# EEZ_DIB_PREL6_r1B4.net
KiCad netlist of a schematic drawn in EAGLE
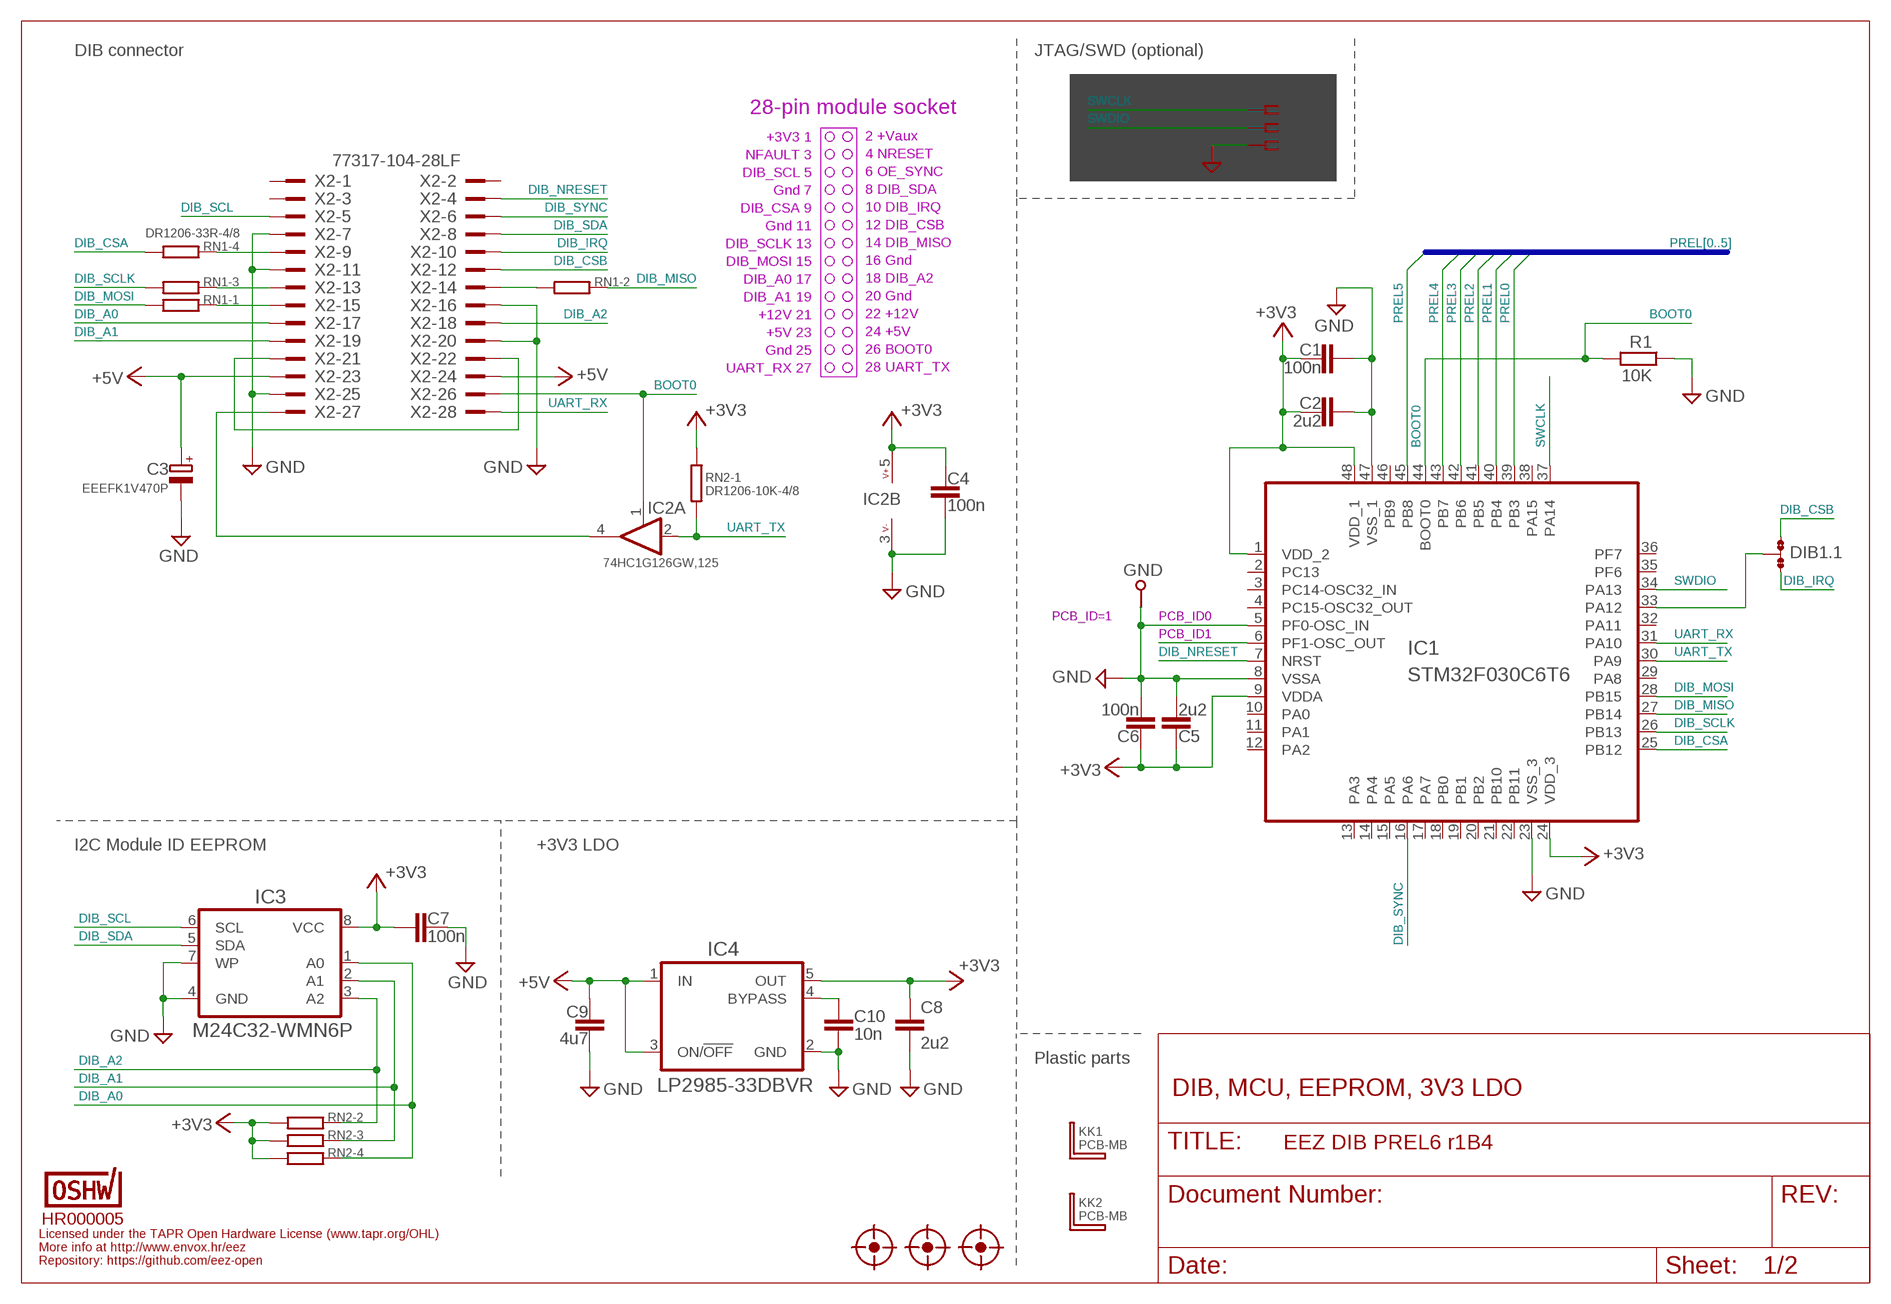
[diagram p0: schematic, sheet 1]
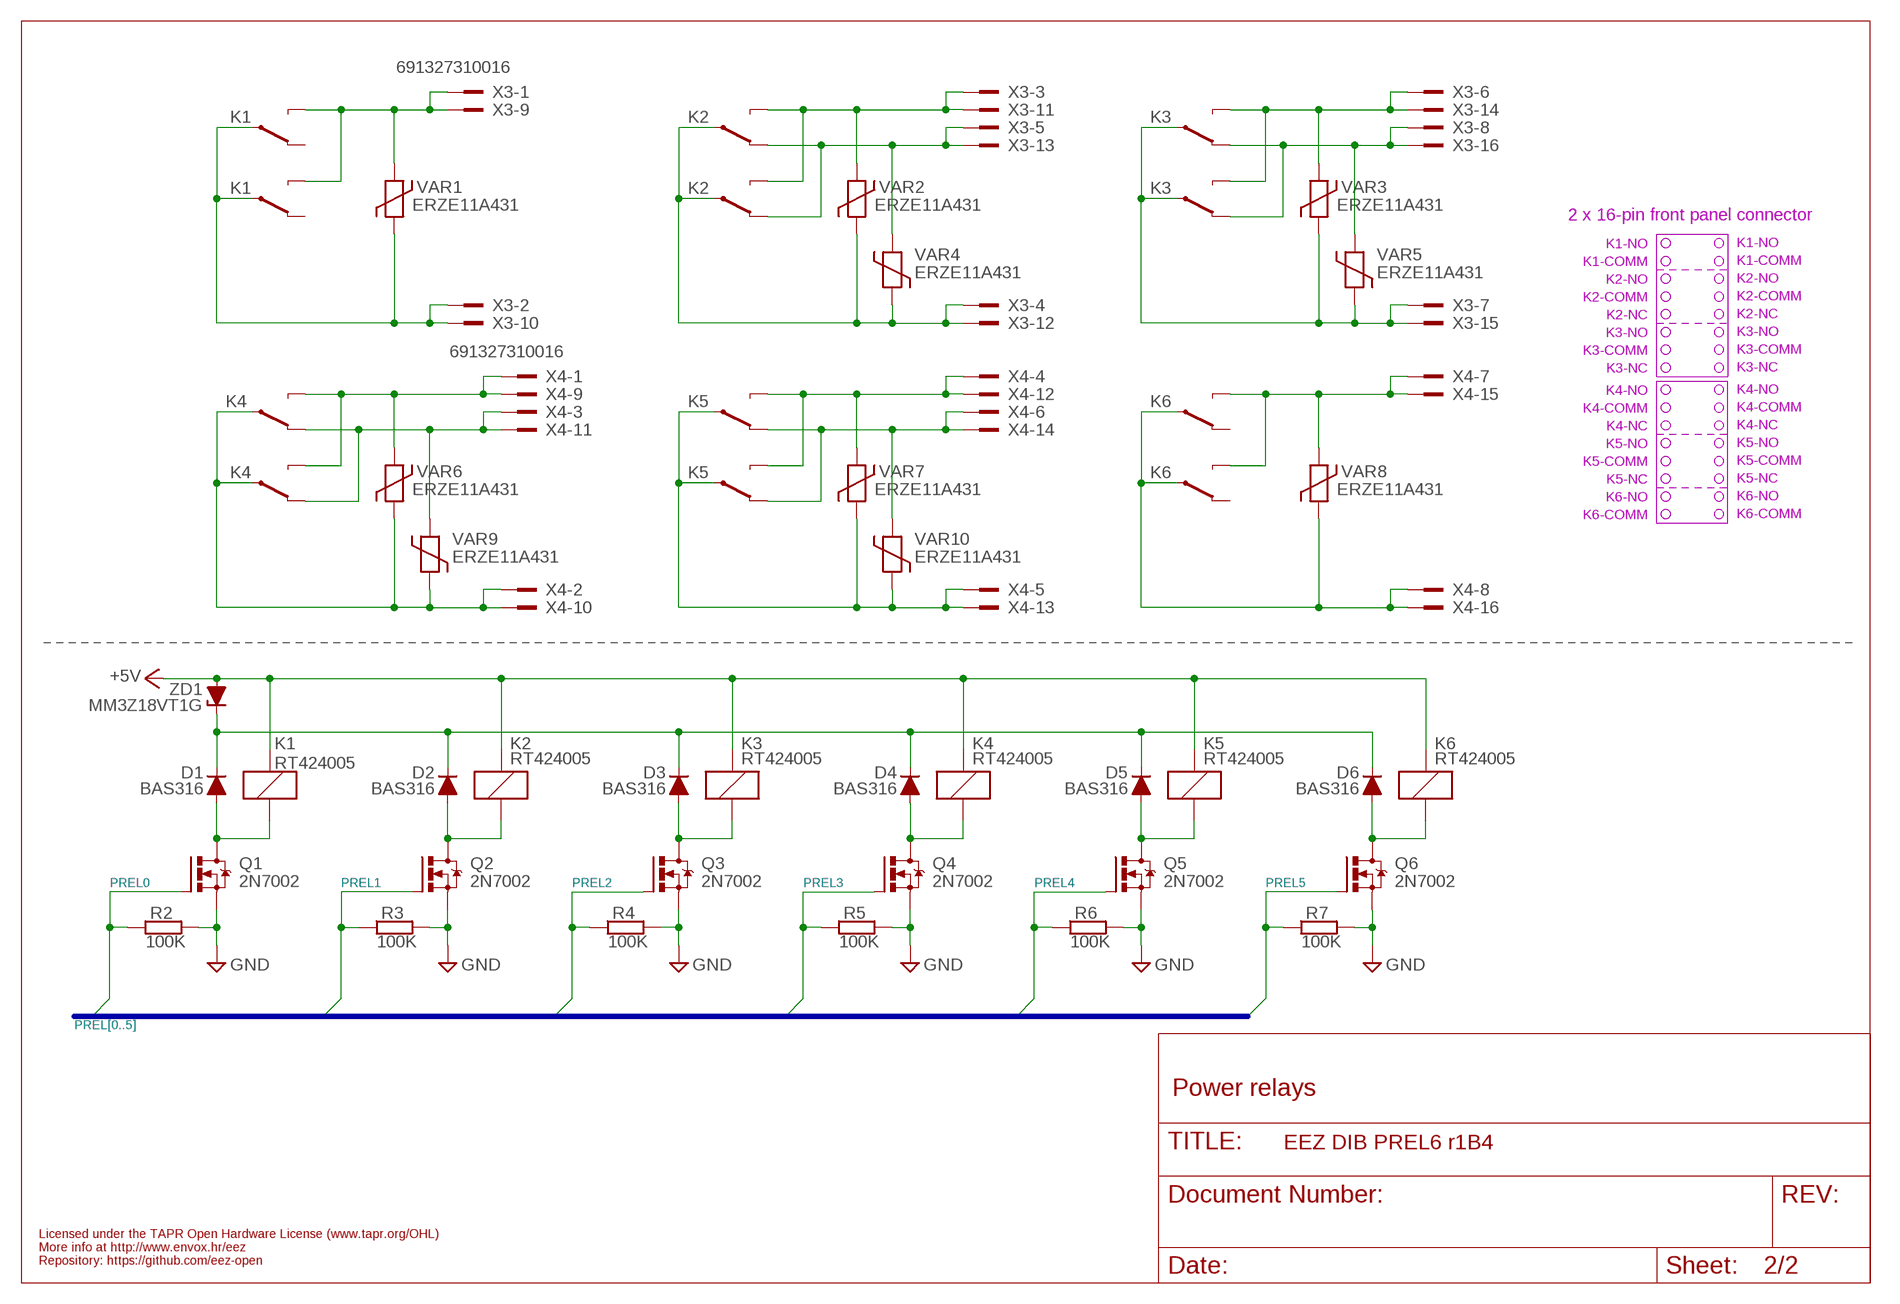
[diagram p1: schematic, sheet 2]

(export (version "E")
  (design (tool "Eeschema 10.0.6"))
  (components
    (comp (ref "C1")
      (value "100n")
      (footprint "eagle-import:C0603")
      (libsource (lib "eagle-import") (part "C-EUC0603"))
    )
    (comp (ref "C2")
      (value "2u2")
      (footprint "eagle-import:C0805")
      (libsource (lib "eagle-import") (part "C-EUC0805"))
    )
    (comp (ref "C3")
      (value "EEEFK1V470P")
      (footprint "eagle-import:CAPAE660X610N")
      (libsource (lib "eagle-import") (part "ECAPPANASONIC_H"))
    )
    (comp (ref "C4")
      (value "100n")
      (footprint "eagle-import:C0603")
      (libsource (lib "eagle-import") (part "C-EUC0603"))
    )
    (comp (ref "C5")
      (value "2u2")
      (footprint "eagle-import:C0805")
      (libsource (lib "eagle-import") (part "C-EUC0805"))
    )
    (comp (ref "C6")
      (value "100n")
      (footprint "eagle-import:C0603")
      (libsource (lib "eagle-import") (part "C-EUC0603"))
    )
    (comp (ref "C7")
      (value "100n")
      (footprint "eagle-import:C0603")
      (libsource (lib "eagle-import") (part "C-EUC0603"))
    )
    (comp (ref "C8")
      (value "2u2")
      (footprint "eagle-import:C0805")
      (libsource (lib "eagle-import") (part "C-EUC0805"))
    )
    (comp (ref "C9")
      (value "4u7")
      (footprint "eagle-import:C0805")
      (libsource (lib "eagle-import") (part "C-EUC0805"))
    )
    (comp (ref "C10")
      (value "10n")
      (footprint "eagle-import:C0805")
      (libsource (lib "eagle-import") (part "C-EUC0805"))
    )
    (comp (ref "DIB1.1")
      (value "JP3-CUT-0805-ROTATED")
      (footprint "eagle-import:JP3-0805-CUT2")
      (libsource (lib "eagle-import") (part "JP3-CUT-0805-ROTATED"))
    )
    (comp (ref "FM1")
      (value "FIDUCIAL_2")
      (footprint "eagle-import:FIDUCIAL_DUAL")
      (libsource (lib "eagle-import") (part "FIDUCIAL_2"))
    )
    (comp (ref "FM2")
      (value "FIDUCIAL_2")
      (footprint "eagle-import:FIDUCIAL_DUAL")
      (libsource (lib "eagle-import") (part "FIDUCIAL_2"))
    )
    (comp (ref "FM3")
      (value "FIDUCIAL_2")
      (footprint "eagle-import:FIDUCIAL_DUAL")
      (libsource (lib "eagle-import") (part "FIDUCIAL_2"))
    )
    (comp (ref "GND")
      (value "PCB_TEST_TABSHIELD")
      (footprint "eagle-import:PCB_SHIELD_TAB")
      (libsource (lib "eagle-import") (part "PCB_TEST_TABSHIELD"))
    )
    (comp (ref "IC1")
      (value "STM32F030C6T6")
      (footprint "eagle-import:LQFP-48")
      (libsource (lib "eagle-import") (part "STM32F030C6T6"))
    )
    (comp (ref "IC2")
      (value "74HC1G126GW,125")
      (footprint "eagle-import:SOT65P210X110-5N")
      (libsource (lib "eagle-import") (part "74HC1G126GW,125"))
    )
    (comp (ref "IC3")
      (value "M24C32-WMN6P")
      (footprint "eagle-import:SOIC127P600X173-8N")
      (libsource (lib "eagle-import") (part "AT24CXXSOIC8"))
    )
    (comp (ref "IC4")
      (value "LP2985-33DBVR")
      (footprint "eagle-import:SOT95P270X145-5N")
      (libsource (lib "eagle-import") (part "LP2985"))
    )
    (comp (ref "KK1")
      (value "PCB-MB")
      (footprint "eagle-import:PCB-MB")
      (libsource (lib "eagle-import") (part "PCB-MB"))
    )
    (comp (ref "KK2")
      (value "PCB-MB")
      (footprint "eagle-import:PCB-MB")
      (libsource (lib "eagle-import") (part "PCB-MB"))
    )
    (comp (ref "R1")
      (value "10K")
      (footprint "eagle-import:R0805")
      (libsource (lib "eagle-import") (part "R-EU_R0805"))
    )
    (comp (ref "RN1")
      (value "DR1206-33R-4/8")
      (footprint "eagle-import:CAY16")
      (libsource (lib "eagle-import") (part "R_ARRAY4"))
    )
    (comp (ref "RN2")
      (value "DR1206-10K-4/8")
      (footprint "eagle-import:CAY16")
      (libsource (lib "eagle-import") (part "R_ARRAY4"))
    )
    (comp (ref "U$3")
      (value "HR000005")
      (footprint "eagle-import:CERT-SMALL-SILK")
      (libsource (lib "eagle-import") (part "CERT-SMALL"))
    )
    (comp (ref "X1")
      (value "N.C.")
      (footprint "eagle-import:SSW-106-02-S-S")
      (fields (field (name "MPN") "SSW-106-02-S-S"))
      (libsource (lib "eagle-import") (part "SSW-106-02-S-S"))
    )
    (comp (ref "X2")
      (value "77317-104-28LF")
      (footprint "eagle-import:77317-104-28LF")
      (libsource (lib "eagle-import") (part "77317-104-28LF"))
    )
    (comp (ref "D1")
      (value "BAS316")
      (footprint "eagle-import:SOD323-R")
      (libsource (lib "eagle-import") (part "DIODESOD323R"))
    )
    (comp (ref "D2")
      (value "BAS316")
      (footprint "eagle-import:SOD323-R")
      (libsource (lib "eagle-import") (part "DIODESOD323R"))
    )
    (comp (ref "D3")
      (value "BAS316")
      (footprint "eagle-import:SOD323-R")
      (libsource (lib "eagle-import") (part "DIODESOD323R"))
    )
    (comp (ref "D4")
      (value "BAS316")
      (footprint "eagle-import:SOD323-R")
      (libsource (lib "eagle-import") (part "DIODESOD323R"))
    )
    (comp (ref "D5")
      (value "BAS316")
      (footprint "eagle-import:SOD323-R")
      (libsource (lib "eagle-import") (part "DIODESOD323R"))
    )
    (comp (ref "D6")
      (value "BAS316")
      (footprint "eagle-import:SOD323-R")
      (libsource (lib "eagle-import") (part "DIODESOD323R"))
    )
    (comp (ref "K1")
      (value "RT424005")
      (footprint "eagle-import:RT-C_016A5_ROUND")
      (libsource (lib "eagle-import") (part "RELAY_RT314012-2"))
    )
    (comp (ref "K2")
      (value "RT424005")
      (footprint "eagle-import:RT-C_016A5_ROUND")
      (libsource (lib "eagle-import") (part "RELAY_RT314012-2"))
    )
    (comp (ref "K3")
      (value "RT424005")
      (footprint "eagle-import:RT-C_016A5_ROUND")
      (libsource (lib "eagle-import") (part "RELAY_RT314012-2"))
    )
    (comp (ref "K4")
      (value "RT424005")
      (footprint "eagle-import:RT-C_016A5_ROUND")
      (libsource (lib "eagle-import") (part "RELAY_RT314012-2"))
    )
    (comp (ref "K5")
      (value "RT424005")
      (footprint "eagle-import:RT-C_016A5_ROUND")
      (libsource (lib "eagle-import") (part "RELAY_RT314012-2"))
    )
    (comp (ref "K6")
      (value "RT424005")
      (footprint "eagle-import:RT-C_016A5_ROUND")
      (libsource (lib "eagle-import") (part "RELAY_RT314012-2"))
    )
    (comp (ref "Q1")
      (value "2N7002")
      (footprint "eagle-import:SOT103P240X110-3N")
      (fields
        (field (name "MPN") "2N7002-7-F")
        (field (name "MPN_1") "2N7002-7-F")
        (field (name "OC_FARNELL") "1713823")
        (field (name "OC_NEWARK") "25R5679")
        (field (name "PACKAGE") "SOT-23-3")
        (field (name "SUPPLIER") "DIODES INC.")
      )
      (libsource (lib "eagle-import") (part "2N7002"))
    )
    (comp (ref "Q2")
      (value "2N7002")
      (footprint "eagle-import:SOT103P240X110-3N")
      (fields
        (field (name "MPN") "2N7002-7-F")
        (field (name "MPN_1") "2N7002-7-F")
        (field (name "OC_FARNELL") "1713823")
        (field (name "OC_NEWARK") "25R5679")
        (field (name "PACKAGE") "SOT-23-3")
        (field (name "SUPPLIER") "DIODES INC.")
      )
      (libsource (lib "eagle-import") (part "2N7002"))
    )
    (comp (ref "Q3")
      (value "2N7002")
      (footprint "eagle-import:SOT103P240X110-3N")
      (fields
        (field (name "MPN") "2N7002-7-F")
        (field (name "MPN_1") "2N7002-7-F")
        (field (name "OC_FARNELL") "1713823")
        (field (name "OC_NEWARK") "25R5679")
        (field (name "PACKAGE") "SOT-23-3")
        (field (name "SUPPLIER") "DIODES INC.")
      )
      (libsource (lib "eagle-import") (part "2N7002"))
    )
    (comp (ref "Q4")
      (value "2N7002")
      (footprint "eagle-import:SOT103P240X110-3N")
      (fields
        (field (name "MPN") "2N7002-7-F")
        (field (name "MPN_1") "2N7002-7-F")
        (field (name "OC_FARNELL") "1713823")
        (field (name "OC_NEWARK") "25R5679")
        (field (name "PACKAGE") "SOT-23-3")
        (field (name "SUPPLIER") "DIODES INC.")
      )
      (libsource (lib "eagle-import") (part "2N7002"))
    )
    (comp (ref "Q5")
      (value "2N7002")
      (footprint "eagle-import:SOT103P240X110-3N")
      (fields
        (field (name "MPN") "2N7002-7-F")
        (field (name "MPN_1") "2N7002-7-F")
        (field (name "OC_FARNELL") "1713823")
        (field (name "OC_NEWARK") "25R5679")
        (field (name "PACKAGE") "SOT-23-3")
        (field (name "SUPPLIER") "DIODES INC.")
      )
      (libsource (lib "eagle-import") (part "2N7002"))
    )
    (comp (ref "Q6")
      (value "2N7002")
      (footprint "eagle-import:SOT103P240X110-3N")
      (fields
        (field (name "MPN") "2N7002-7-F")
        (field (name "MPN_1") "2N7002-7-F")
        (field (name "OC_FARNELL") "1713823")
        (field (name "OC_NEWARK") "25R5679")
        (field (name "PACKAGE") "SOT-23-3")
        (field (name "SUPPLIER") "DIODES INC.")
      )
      (libsource (lib "eagle-import") (part "2N7002"))
    )
    (comp (ref "R2")
      (value "100K")
      (footprint "eagle-import:R0805")
      (libsource (lib "eagle-import") (part "R-EU_R0805"))
    )
    (comp (ref "R3")
      (value "100K")
      (footprint "eagle-import:R0805")
      (libsource (lib "eagle-import") (part "R-EU_R0805"))
    )
    (comp (ref "R4")
      (value "100K")
      (footprint "eagle-import:R0805")
      (libsource (lib "eagle-import") (part "R-EU_R0805"))
    )
    (comp (ref "R5")
      (value "100K")
      (footprint "eagle-import:R0805")
      (libsource (lib "eagle-import") (part "R-EU_R0805"))
    )
    (comp (ref "R6")
      (value "100K")
      (footprint "eagle-import:R0805")
      (libsource (lib "eagle-import") (part "R-EU_R0805"))
    )
    (comp (ref "R7")
      (value "100K")
      (footprint "eagle-import:R0805")
      (libsource (lib "eagle-import") (part "R-EU_R0805"))
    )
    (comp (ref "VAR1")
      (value "ERZE11A431")
      (footprint "eagle-import:VARISTOR_13MM")
      (libsource (lib "eagle-import") (part "VARISTOR-13"))
    )
    (comp (ref "VAR2")
      (value "ERZE11A431")
      (footprint "eagle-import:VARISTOR_13MM")
      (libsource (lib "eagle-import") (part "VARISTOR-13"))
    )
    (comp (ref "VAR3")
      (value "ERZE11A431")
      (footprint "eagle-import:VARISTOR_13MM")
      (libsource (lib "eagle-import") (part "VARISTOR-13"))
    )
    (comp (ref "VAR4")
      (value "ERZE11A431")
      (footprint "eagle-import:VARISTOR_13MM")
      (libsource (lib "eagle-import") (part "VARISTOR-13"))
    )
    (comp (ref "VAR5")
      (value "ERZE11A431")
      (footprint "eagle-import:VARISTOR_13MM")
      (libsource (lib "eagle-import") (part "VARISTOR-13"))
    )
    (comp (ref "VAR6")
      (value "ERZE11A431")
      (footprint "eagle-import:VARISTOR_13MM")
      (libsource (lib "eagle-import") (part "VARISTOR-13"))
    )
    (comp (ref "VAR7")
      (value "ERZE11A431")
      (footprint "eagle-import:VARISTOR_13MM")
      (libsource (lib "eagle-import") (part "VARISTOR-13"))
    )
    (comp (ref "VAR8")
      (value "ERZE11A431")
      (footprint "eagle-import:VARISTOR_13MM")
      (libsource (lib "eagle-import") (part "VARISTOR-13"))
    )
    (comp (ref "VAR9")
      (value "ERZE11A431")
      (footprint "eagle-import:VARISTOR_13MM")
      (libsource (lib "eagle-import") (part "VARISTOR-13"))
    )
    (comp (ref "VAR10")
      (value "ERZE11A431")
      (footprint "eagle-import:VARISTOR_13MM")
      (libsource (lib "eagle-import") (part "VARISTOR-13"))
    )
    (comp (ref "X3")
      (value "691327310016")
      (footprint "eagle-import:691327310016")
      (libsource (lib "eagle-import") (part "691327310016"))
    )
    (comp (ref "X4")
      (value "691327310016")
      (footprint "eagle-import:691327310016")
      (libsource (lib "eagle-import") (part "691327310016"))
    )
    (comp (ref "ZD1")
      (value "MM3Z18VT1G")
      (footprint "eagle-import:SOD323-R")
      (libsource (lib "eagle-import") (part "ZENER-DIODESOD323R"))
    )
  )
  (nets
    (net (code "1") (name "+3V3") (class "Default")
      (node (ref "C1") (pin "2") (pinfunction "2_2") (pintype "passive"))
      (node (ref "C2") (pin "1") (pinfunction "1_1") (pintype "passive"))
      (node (ref "C4") (pin "1") (pinfunction "1_1") (pintype "passive"))
      (node (ref "C5") (pin "2") (pinfunction "2_2") (pintype "passive"))
      (node (ref "C6") (pin "1") (pinfunction "1_1") (pintype "passive"))
      (node (ref "C7") (pin "2") (pinfunction "2_2") (pintype "passive"))
      (node (ref "C8") (pin "1") (pinfunction "1_1") (pintype "passive"))
      (node (ref "IC1") (pin "1") (pinfunction "VDD_2_1") (pintype "passive"))
      (node (ref "IC1") (pin "24") (pinfunction "VDD_3_24") (pintype "passive"))
      (node (ref "IC1") (pin "48") (pinfunction "VDD_1_48") (pintype "passive"))
      (node (ref "IC1") (pin "9") (pinfunction "VDDA_9") (pintype "passive"))
      (node (ref "IC2") (pin "5") (pinfunction "V+_5") (pintype "power_in"))
      (node (ref "IC3") (pin "8") (pinfunction "VCC_8") (pintype "power_in"))
      (node (ref "IC4") (pin "5") (pinfunction "OUT_5") (pintype "passive"))
      (node (ref "RN2") (pin "5") (pinfunction "2_5") (pintype "passive"))
      (node (ref "RN2") (pin "6") (pinfunction "2_6") (pintype "passive"))
      (node (ref "RN2") (pin "7") (pinfunction "2_7") (pintype "passive"))
      (node (ref "RN2") (pin "8") (pinfunction "2_8") (pintype "passive"))
    )
    (net (code "2") (name "+5V") (class "Default")
      (node (ref "C3") (pin "1") (pinfunction "+_1") (pintype "passive"))
      (node (ref "C9") (pin "2") (pinfunction "2_2") (pintype "passive"))
      (node (ref "IC4") (pin "1") (pinfunction "IN_1") (pintype "input"))
      (node (ref "IC4") (pin "3") (pinfunction "ON/~{OFF}_3") (pintype "input"))
      (node (ref "K1") (pin "A2") (pinfunction "C1_A2") (pintype "passive"))
      (node (ref "K2") (pin "A2") (pinfunction "C1_A2") (pintype "passive"))
      (node (ref "K3") (pin "A2") (pinfunction "C1_A2") (pintype "passive"))
      (node (ref "K4") (pin "A2") (pinfunction "C1_A2") (pintype "passive"))
      (node (ref "K5") (pin "A2") (pinfunction "C1_A2") (pintype "passive"))
      (node (ref "K6") (pin "A2") (pinfunction "C1_A2") (pintype "passive"))
      (node (ref "X2") (pin "23") (pinfunction "1_23") (pintype "passive"))
      (node (ref "X2") (pin "24") (pinfunction "1_24") (pintype "passive"))
      (node (ref "ZD1") (pin "A") (pinfunction "A_A") (pintype "passive"))
    )
    (net (code "5") (name "BOOT0") (class "Default")
      (node (ref "IC1") (pin "44") (pinfunction "BOOT0_44") (pintype "input"))
      (node (ref "IC2") (pin "1") (pinfunction "EN_1") (pintype "input"))
      (node (ref "R1") (pin "2") (pinfunction "2_2") (pintype "passive"))
      (node (ref "X2") (pin "26") (pinfunction "1_26") (pintype "passive"))
    )
    (net (code "6") (name "DIB_A0") (class "Default")
      (node (ref "IC3") (pin "1") (pinfunction "A0_1") (pintype "input"))
      (node (ref "RN2") (pin "4") (pinfunction "1_4") (pintype "passive"))
      (node (ref "X2") (pin "17") (pinfunction "1_17") (pintype "passive"))
    )
    (net (code "7") (name "DIB_A1") (class "Default")
      (node (ref "IC3") (pin "2") (pinfunction "A1_2") (pintype "input"))
      (node (ref "RN2") (pin "3") (pinfunction "1_3") (pintype "passive"))
      (node (ref "X2") (pin "19") (pinfunction "1_19") (pintype "passive"))
    )
    (net (code "8") (name "DIB_A2") (class "Default")
      (node (ref "IC3") (pin "3") (pinfunction "A2_3") (pintype "input"))
      (node (ref "RN2") (pin "2") (pinfunction "1_2") (pintype "passive"))
      (node (ref "X2") (pin "18") (pinfunction "1_18") (pintype "passive"))
    )
    (net (code "9") (name "DIB_CSA") (class "Default")
      (node (ref "IC1") (pin "25") (pinfunction "PB12_25") (pintype "bidirectional"))
      (node (ref "RN1") (pin "4") (pinfunction "1_4") (pintype "passive"))
    )
    (net (code "10") (name "DIB_CSB") (class "Default")
      (node (ref "DIB1.1") (pin "NO") (pinfunction "NO_NO") (pintype "passive"))
      (node (ref "X2") (pin "12") (pinfunction "1_12") (pintype "passive"))
    )
    (net (code "11") (name "DIB_IRQ") (class "Default")
      (node (ref "DIB1.1") (pin "NC") (pinfunction "NC_NC") (pintype "passive"))
      (node (ref "X2") (pin "10") (pinfunction "1_10") (pintype "passive"))
    )
    (net (code "12") (name "DIB_MISO") (class "Default")
      (node (ref "IC1") (pin "27") (pinfunction "PB14_27") (pintype "bidirectional"))
      (node (ref "RN1") (pin "2") (pinfunction "1_2") (pintype "passive"))
    )
    (net (code "13") (name "DIB_MOSI") (class "Default")
      (node (ref "IC1") (pin "28") (pinfunction "PB15_28") (pintype "bidirectional"))
      (node (ref "RN1") (pin "1") (pinfunction "1_1") (pintype "passive"))
    )
    (net (code "14") (name "DIB_NRESET") (class "Default")
      (node (ref "IC1") (pin "7") (pinfunction "NRST_7") (pintype "input"))
      (node (ref "X2") (pin "4") (pinfunction "1_4") (pintype "passive"))
    )
    (net (code "15") (name "DIB_SCL") (class "Default")
      (node (ref "IC3") (pin "6") (pinfunction "SCL_6") (pintype "bidirectional"))
      (node (ref "X2") (pin "5") (pinfunction "1_5") (pintype "passive"))
    )
    (net (code "16") (name "DIB_SCLK") (class "Default")
      (node (ref "IC1") (pin "26") (pinfunction "PB13_26") (pintype "bidirectional"))
      (node (ref "RN1") (pin "3") (pinfunction "1_3") (pintype "passive"))
    )
    (net (code "17") (name "DIB_SDA") (class "Default")
      (node (ref "IC3") (pin "5") (pinfunction "SDA_5") (pintype "bidirectional"))
      (node (ref "X2") (pin "8") (pinfunction "1_8") (pintype "passive"))
    )
    (net (code "18") (name "DIB_SYNC") (class "Default")
      (node (ref "IC1") (pin "16") (pinfunction "PA6_16") (pintype "bidirectional"))
      (node (ref "X2") (pin "6") (pinfunction "1_6") (pintype "passive"))
    )
    (net (code "19") (name "GND") (class "Default")
      (node (ref "C1") (pin "1") (pinfunction "1_1") (pintype "passive"))
      (node (ref "C10") (pin "1") (pinfunction "1_1") (pintype "passive"))
      (node (ref "C2") (pin "2") (pinfunction "2_2") (pintype "passive"))
      (node (ref "C3") (pin "2") (pinfunction "-_2") (pintype "passive"))
      (node (ref "C4") (pin "2") (pinfunction "2_2") (pintype "passive"))
      (node (ref "C5") (pin "1") (pinfunction "1_1") (pintype "passive"))
      (node (ref "C6") (pin "2") (pinfunction "2_2") (pintype "passive"))
      (node (ref "C7") (pin "1") (pinfunction "1_1") (pintype "passive"))
      (node (ref "C8") (pin "2") (pinfunction "2_2") (pintype "passive"))
      (node (ref "C9") (pin "1") (pinfunction "1_1") (pintype "passive"))
      (node (ref "GND") (pin "1") (pinfunction "P$1_1") (pintype "bidirectional"))
      (node (ref "IC1") (pin "23") (pinfunction "VSS_3_23") (pintype "passive"))
      (node (ref "IC1") (pin "47") (pinfunction "VSS_1_47") (pintype "passive"))
      (node (ref "IC1") (pin "5") (pinfunction "PF0-OSC_IN_5") (pintype "bidirectional"))
      (node (ref "IC1") (pin "8") (pinfunction "VSSA_8") (pintype "passive"))
      (node (ref "IC2") (pin "3") (pinfunction "V-_3") (pintype "power_in"))
      (node (ref "IC3") (pin "4") (pinfunction "GND_4") (pintype "passive"))
      (node (ref "IC3") (pin "7") (pinfunction "WP_7") (pintype "input"))
      (node (ref "IC4") (pin "2") (pinfunction "GND_2") (pintype "passive"))
      (node (ref "Q1") (pin "2") (pinfunction "S_2") (pintype "passive"))
      (node (ref "Q2") (pin "2") (pinfunction "S_2") (pintype "passive"))
      (node (ref "Q3") (pin "2") (pinfunction "S_2") (pintype "passive"))
      (node (ref "Q4") (pin "2") (pinfunction "S_2") (pintype "passive"))
      (node (ref "Q5") (pin "2") (pinfunction "S_2") (pintype "passive"))
      (node (ref "Q6") (pin "2") (pinfunction "S_2") (pintype "passive"))
      (node (ref "R1") (pin "1") (pinfunction "1_1") (pintype "passive"))
      (node (ref "R2") (pin "2") (pinfunction "2_2") (pintype "passive"))
      (node (ref "R3") (pin "2") (pinfunction "2_2") (pintype "passive"))
      (node (ref "R4") (pin "2") (pinfunction "2_2") (pintype "passive"))
      (node (ref "R5") (pin "2") (pinfunction "2_2") (pintype "passive"))
      (node (ref "R6") (pin "2") (pinfunction "2_2") (pintype "passive"))
      (node (ref "R7") (pin "2") (pinfunction "2_2") (pintype "passive"))
      (node (ref "X1") (pin "3") (pinfunction "1_3") (pintype "passive"))
      (node (ref "X2") (pin "11") (pinfunction "1_11") (pintype "passive"))
      (node (ref "X2") (pin "16") (pinfunction "1_16") (pintype "passive"))
      (node (ref "X2") (pin "20") (pinfunction "1_20") (pintype "passive"))
      (node (ref "X2") (pin "25") (pinfunction "1_25") (pintype "passive"))
      (node (ref "X2") (pin "7") (pinfunction "1_7") (pintype "passive"))
    )
    (net (code "20") (name "Net-(D1-PadC)") (class "Default")
      (node (ref "D1") (pin "C") (pinfunction "C_C") (pintype "passive"))
      (node (ref "D2") (pin "C") (pinfunction "C_C") (pintype "passive"))
      (node (ref "D3") (pin "C") (pinfunction "C_C") (pintype "passive"))
      (node (ref "D4") (pin "C") (pinfunction "C_C") (pintype "passive"))
      (node (ref "D5") (pin "C") (pinfunction "C_C") (pintype "passive"))
      (node (ref "D6") (pin "C") (pinfunction "C_C") (pintype "passive"))
      (node (ref "ZD1") (pin "C") (pinfunction "C_C") (pintype "passive"))
    )
    (net (code "21") (name "Net-(IC1-PA12)") (class "Default")
      (node (ref "DIB1.1") (pin "COM") (pinfunction "COM_COM") (pintype "passive"))
      (node (ref "IC1") (pin "33") (pinfunction "PA12_33") (pintype "bidirectional"))
    )
    (net (code "22") (name "Net-(IC2A-O)") (class "Default")
      (node (ref "IC2") (pin "4") (pinfunction "O_4") (pintype "output"))
      (node (ref "X2") (pin "27") (pinfunction "1_27") (pintype "passive"))
    )
    (net (code "23") (name "Net-(IC4-BYPASS)") (class "Default")
      (node (ref "C10") (pin "2") (pinfunction "2_2") (pintype "passive"))
      (node (ref "IC4") (pin "4") (pinfunction "BYPASS_4") (pintype "passive"))
    )
    (net (code "24") (name "Net-(K1A-O)") (class "Default")
      (node (ref "K1") (pin "14A") (pinfunction "O_14A") (pintype "passive"))
      (node (ref "K1") (pin "14B") (pinfunction "O_14B") (pintype "passive"))
      (node (ref "VAR1") (pin "2") (pinfunction "P$2_2") (pintype "bidirectional"))
      (node (ref "X3") (pin "1") (pinfunction "1_1") (pintype "passive"))
      (node (ref "X3") (pin "9") (pinfunction "1_9") (pintype "passive"))
    )
    (net (code "25") (name "Net-(K1A-P)") (class "Default")
      (node (ref "K1") (pin "11A") (pinfunction "P_11A") (pintype "passive"))
      (node (ref "K1") (pin "11B") (pinfunction "P_11B") (pintype "passive"))
      (node (ref "VAR1") (pin "1") (pinfunction "P$1_1") (pintype "bidirectional"))
      (node (ref "X3") (pin "10") (pinfunction "1_10") (pintype "passive"))
      (node (ref "X3") (pin "2") (pinfunction "1_2") (pintype "passive"))
    )
    (net (code "26") (name "Net-(K1C-C2)") (class "Default")
      (node (ref "D1") (pin "A") (pinfunction "A_A") (pintype "passive"))
      (node (ref "K1") (pin "A1") (pinfunction "C2_A1") (pintype "passive"))
      (node (ref "Q1") (pin "3") (pinfunction "D_3") (pintype "passive"))
    )
    (net (code "27") (name "Net-(K2A-O)") (class "Default")
      (node (ref "K2") (pin "14A") (pinfunction "O_14A") (pintype "passive"))
      (node (ref "K2") (pin "14B") (pinfunction "O_14B") (pintype "passive"))
      (node (ref "VAR2") (pin "2") (pinfunction "P$2_2") (pintype "bidirectional"))
      (node (ref "X3") (pin "11") (pinfunction "1_11") (pintype "passive"))
      (node (ref "X3") (pin "3") (pinfunction "1_3") (pintype "passive"))
    )
    (net (code "28") (name "Net-(K2A-P)") (class "Default")
      (node (ref "K2") (pin "11A") (pinfunction "P_11A") (pintype "passive"))
      (node (ref "K2") (pin "11B") (pinfunction "P_11B") (pintype "passive"))
      (node (ref "VAR2") (pin "1") (pinfunction "P$1_1") (pintype "bidirectional"))
      (node (ref "VAR4") (pin "1") (pinfunction "P$1_1") (pintype "bidirectional"))
      (node (ref "X3") (pin "12") (pinfunction "1_12") (pintype "passive"))
      (node (ref "X3") (pin "4") (pinfunction "1_4") (pintype "passive"))
    )
    (net (code "29") (name "Net-(K2A-S)") (class "Default")
      (node (ref "K2") (pin "12A") (pinfunction "S_12A") (pintype "passive"))
      (node (ref "K2") (pin "12B") (pinfunction "S_12B") (pintype "passive"))
      (node (ref "VAR4") (pin "2") (pinfunction "P$2_2") (pintype "bidirectional"))
      (node (ref "X3") (pin "13") (pinfunction "1_13") (pintype "passive"))
      (node (ref "X3") (pin "5") (pinfunction "1_5") (pintype "passive"))
    )
    (net (code "30") (name "Net-(K2C-C2)") (class "Default")
      (node (ref "D2") (pin "A") (pinfunction "A_A") (pintype "passive"))
      (node (ref "K2") (pin "A1") (pinfunction "C2_A1") (pintype "passive"))
      (node (ref "Q2") (pin "3") (pinfunction "D_3") (pintype "passive"))
    )
    (net (code "31") (name "Net-(K3A-O)") (class "Default")
      (node (ref "K3") (pin "14A") (pinfunction "O_14A") (pintype "passive"))
      (node (ref "K3") (pin "14B") (pinfunction "O_14B") (pintype "passive"))
      (node (ref "VAR3") (pin "2") (pinfunction "P$2_2") (pintype "bidirectional"))
      (node (ref "X3") (pin "14") (pinfunction "1_14") (pintype "passive"))
      (node (ref "X3") (pin "6") (pinfunction "1_6") (pintype "passive"))
    )
    (net (code "32") (name "Net-(K3A-P)") (class "Default")
      (node (ref "K3") (pin "11A") (pinfunction "P_11A") (pintype "passive"))
      (node (ref "K3") (pin "11B") (pinfunction "P_11B") (pintype "passive"))
      (node (ref "VAR3") (pin "1") (pinfunction "P$1_1") (pintype "bidirectional"))
      (node (ref "VAR5") (pin "1") (pinfunction "P$1_1") (pintype "bidirectional"))
      (node (ref "X3") (pin "15") (pinfunction "1_15") (pintype "passive"))
      (node (ref "X3") (pin "7") (pinfunction "1_7") (pintype "passive"))
    )
    (net (code "33") (name "Net-(K3A-S)") (class "Default")
      (node (ref "K3") (pin "12A") (pinfunction "S_12A") (pintype "passive"))
      (node (ref "K3") (pin "12B") (pinfunction "S_12B") (pintype "passive"))
      (node (ref "VAR5") (pin "2") (pinfunction "P$2_2") (pintype "bidirectional"))
      (node (ref "X3") (pin "16") (pinfunction "1_16") (pintype "passive"))
      (node (ref "X3") (pin "8") (pinfunction "1_8") (pintype "passive"))
    )
    (net (code "34") (name "Net-(K3C-C2)") (class "Default")
      (node (ref "D3") (pin "A") (pinfunction "A_A") (pintype "passive"))
      (node (ref "K3") (pin "A1") (pinfunction "C2_A1") (pintype "passive"))
      (node (ref "Q3") (pin "3") (pinfunction "D_3") (pintype "passive"))
    )
    (net (code "35") (name "Net-(K4A-O)") (class "Default")
      (node (ref "K4") (pin "14A") (pinfunction "O_14A") (pintype "passive"))
      (node (ref "K4") (pin "14B") (pinfunction "O_14B") (pintype "passive"))
      (node (ref "VAR6") (pin "2") (pinfunction "P$2_2") (pintype "bidirectional"))
      (node (ref "X4") (pin "1") (pinfunction "1_1") (pintype "passive"))
      (node (ref "X4") (pin "9") (pinfunction "1_9") (pintype "passive"))
    )
    (net (code "36") (name "Net-(K4A-P)") (class "Default")
      (node (ref "K4") (pin "11A") (pinfunction "P_11A") (pintype "passive"))
      (node (ref "K4") (pin "11B") (pinfunction "P_11B") (pintype "passive"))
      (node (ref "VAR6") (pin "1") (pinfunction "P$1_1") (pintype "bidirectional"))
      (node (ref "VAR9") (pin "1") (pinfunction "P$1_1") (pintype "bidirectional"))
      (node (ref "X4") (pin "10") (pinfunction "1_10") (pintype "passive"))
      (node (ref "X4") (pin "2") (pinfunction "1_2") (pintype "passive"))
    )
    (net (code "37") (name "Net-(K4A-S)") (class "Default")
      (node (ref "K4") (pin "12A") (pinfunction "S_12A") (pintype "passive"))
      (node (ref "K4") (pin "12B") (pinfunction "S_12B") (pintype "passive"))
      (node (ref "VAR9") (pin "2") (pinfunction "P$2_2") (pintype "bidirectional"))
      (node (ref "X4") (pin "11") (pinfunction "1_11") (pintype "passive"))
      (node (ref "X4") (pin "3") (pinfunction "1_3") (pintype "passive"))
    )
    (net (code "38") (name "Net-(K4C-C2)") (class "Default")
      (node (ref "D4") (pin "A") (pinfunction "A_A") (pintype "passive"))
      (node (ref "K4") (pin "A1") (pinfunction "C2_A1") (pintype "passive"))
      (node (ref "Q4") (pin "3") (pinfunction "D_3") (pintype "passive"))
    )
    (net (code "39") (name "Net-(K5A-O)") (class "Default")
      (node (ref "K5") (pin "14A") (pinfunction "O_14A") (pintype "passive"))
      (node (ref "K5") (pin "14B") (pinfunction "O_14B") (pintype "passive"))
      (node (ref "VAR7") (pin "2") (pinfunction "P$2_2") (pintype "bidirectional"))
      (node (ref "X4") (pin "12") (pinfunction "1_12") (pintype "passive"))
      (node (ref "X4") (pin "4") (pinfunction "1_4") (pintype "passive"))
    )
    (net (code "40") (name "Net-(K5A-P)") (class "Default")
      (node (ref "K5") (pin "11A") (pinfunction "P_11A") (pintype "passive"))
      (node (ref "K5") (pin "11B") (pinfunction "P_11B") (pintype "passive"))
      (node (ref "VAR10") (pin "1") (pinfunction "P$1_1") (pintype "bidirectional"))
      (node (ref "VAR7") (pin "1") (pinfunction "P$1_1") (pintype "bidirectional"))
      (node (ref "X4") (pin "13") (pinfunction "1_13") (pintype "passive"))
      (node (ref "X4") (pin "5") (pinfunction "1_5") (pintype "passive"))
    )
    (net (code "41") (name "Net-(K5A-S)") (class "Default")
      (node (ref "K5") (pin "12A") (pinfunction "S_12A") (pintype "passive"))
      (node (ref "K5") (pin "12B") (pinfunction "S_12B") (pintype "passive"))
      (node (ref "VAR10") (pin "2") (pinfunction "P$2_2") (pintype "bidirectional"))
      (node (ref "X4") (pin "14") (pinfunction "1_14") (pintype "passive"))
      (node (ref "X4") (pin "6") (pinfunction "1_6") (pintype "passive"))
    )
    (net (code "42") (name "Net-(K5C-C2)") (class "Default")
      (node (ref "D5") (pin "A") (pinfunction "A_A") (pintype "passive"))
      (node (ref "K5") (pin "A1") (pinfunction "C2_A1") (pintype "passive"))
      (node (ref "Q5") (pin "3") (pinfunction "D_3") (pintype "passive"))
    )
    (net (code "43") (name "Net-(K6A-O)") (class "Default")
      (node (ref "K6") (pin "14A") (pinfunction "O_14A") (pintype "passive"))
      (node (ref "K6") (pin "14B") (pinfunction "O_14B") (pintype "passive"))
      (node (ref "VAR8") (pin "2") (pinfunction "P$2_2") (pintype "bidirectional"))
      (node (ref "X4") (pin "15") (pinfunction "1_15") (pintype "passive"))
      (node (ref "X4") (pin "7") (pinfunction "1_7") (pintype "passive"))
    )
    (net (code "44") (name "Net-(K6A-P)") (class "Default")
      (node (ref "K6") (pin "11A") (pinfunction "P_11A") (pintype "passive"))
      (node (ref "K6") (pin "11B") (pinfunction "P_11B") (pintype "passive"))
      (node (ref "VAR8") (pin "1") (pinfunction "P$1_1") (pintype "bidirectional"))
      (node (ref "X4") (pin "16") (pinfunction "1_16") (pintype "passive"))
      (node (ref "X4") (pin "8") (pinfunction "1_8") (pintype "passive"))
    )
    (net (code "45") (name "Net-(K6C-C2)") (class "Default")
      (node (ref "D6") (pin "A") (pinfunction "A_A") (pintype "passive"))
      (node (ref "K6") (pin "A1") (pinfunction "C2_A1") (pintype "passive"))
      (node (ref "Q6") (pin "3") (pinfunction "D_3") (pintype "passive"))
    )
    (net (code "46") (name "Net-(RN1A-2)") (class "Default")
      (node (ref "RN1") (pin "8") (pinfunction "2_8") (pintype "passive"))
      (node (ref "X2") (pin "15") (pinfunction "1_15") (pintype "passive"))
    )
    (net (code "47") (name "Net-(RN1B-2)") (class "Default")
      (node (ref "RN1") (pin "7") (pinfunction "2_7") (pintype "passive"))
      (node (ref "X2") (pin "14") (pinfunction "1_14") (pintype "passive"))
    )
    (net (code "48") (name "Net-(RN1C-2)") (class "Default")
      (node (ref "RN1") (pin "6") (pinfunction "2_6") (pintype "passive"))
      (node (ref "X2") (pin "13") (pinfunction "1_13") (pintype "passive"))
    )
    (net (code "49") (name "Net-(RN1D-2)") (class "Default")
      (node (ref "RN1") (pin "5") (pinfunction "2_5") (pintype "passive"))
      (node (ref "X2") (pin "9") (pinfunction "1_9") (pintype "passive"))
    )
    (net (code "50") (name "Net-(X2N-1)") (class "Default")
      (node (ref "X2") (pin "21") (pinfunction "1_21") (pintype "passive"))
      (node (ref "X2") (pin "22") (pinfunction "1_22") (pintype "passive"))
    )
    (net (code "51") (name "PREL0") (class "Default")
      (node (ref "IC1") (pin "39") (pinfunction "PB3_39") (pintype "bidirectional"))
      (node (ref "Q1") (pin "1") (pinfunction "G_1") (pintype "passive"))
      (node (ref "R2") (pin "1") (pinfunction "1_1") (pintype "passive"))
    )
    (net (code "52") (name "PREL1") (class "Default")
      (node (ref "IC1") (pin "40") (pinfunction "PB4_40") (pintype "bidirectional"))
      (node (ref "Q2") (pin "1") (pinfunction "G_1") (pintype "passive"))
      (node (ref "R3") (pin "1") (pinfunction "1_1") (pintype "passive"))
    )
    (net (code "53") (name "PREL2") (class "Default")
      (node (ref "IC1") (pin "41") (pinfunction "PB5_41") (pintype "bidirectional"))
      (node (ref "Q3") (pin "1") (pinfunction "G_1") (pintype "passive"))
      (node (ref "R4") (pin "1") (pinfunction "1_1") (pintype "passive"))
    )
    (net (code "54") (name "PREL3") (class "Default")
      (node (ref "IC1") (pin "42") (pinfunction "PB6_42") (pintype "bidirectional"))
      (node (ref "Q4") (pin "1") (pinfunction "G_1") (pintype "passive"))
      (node (ref "R5") (pin "1") (pinfunction "1_1") (pintype "passive"))
    )
    (net (code "55") (name "PREL4") (class "Default")
      (node (ref "IC1") (pin "43") (pinfunction "PB7_43") (pintype "bidirectional"))
      (node (ref "Q5") (pin "1") (pinfunction "G_1") (pintype "passive"))
      (node (ref "R6") (pin "1") (pinfunction "1_1") (pintype "passive"))
    )
    (net (code "56") (name "PREL5") (class "Default")
      (node (ref "IC1") (pin "45") (pinfunction "PB8_45") (pintype "bidirectional"))
      (node (ref "Q6") (pin "1") (pinfunction "G_1") (pintype "passive"))
      (node (ref "R7") (pin "1") (pinfunction "1_1") (pintype "passive"))
    )
    (net (code "57") (name "SWCLK") (class "Default")
      (node (ref "IC1") (pin "37") (pinfunction "PA14_37") (pintype "bidirectional"))
      (node (ref "X1") (pin "2") (pinfunction "1_2") (pintype "passive"))
    )
    (net (code "58") (name "SWDIO") (class "Default")
      (node (ref "IC1") (pin "34") (pinfunction "PA13_34") (pintype "bidirectional"))
      (node (ref "X1") (pin "4") (pinfunction "1_4") (pintype "passive"))
    )
    (net (code "59") (name "UART_RX") (class "Default")
      (node (ref "IC1") (pin "31") (pinfunction "PA10_31") (pintype "bidirectional"))
      (node (ref "X2") (pin "28") (pinfunction "1_28") (pintype "passive"))
    )
    (net (code "60") (name "UART_TX") (class "Default")
      (node (ref "IC1") (pin "30") (pinfunction "PA9_30") (pintype "bidirectional"))
      (node (ref "IC2") (pin "2") (pinfunction "I_2") (pintype "input"))
      (node (ref "RN2") (pin "1") (pinfunction "1_1") (pintype "passive"))
    )
    (net (code "61") (name "unconnected-(IC1-PA0-Pad10)") (class "Default")
      (node (ref "IC1") (pin "10") (pinfunction "PA0_10") (pintype "bidirectional"))
    )
    (net (code "62") (name "unconnected-(IC1-PA1-Pad11)") (class "Default")
      (node (ref "IC1") (pin "11") (pinfunction "PA1_11") (pintype "bidirectional"))
    )
    (net (code "63") (name "unconnected-(IC1-PA2-Pad12)") (class "Default")
      (node (ref "IC1") (pin "12") (pinfunction "PA2_12") (pintype "bidirectional"))
    )
    (net (code "64") (name "unconnected-(IC1-PA3-Pad13)") (class "Default")
      (node (ref "IC1") (pin "13") (pinfunction "PA3_13") (pintype "bidirectional"))
    )
    (net (code "65") (name "unconnected-(IC1-PA4-Pad14)") (class "Default")
      (node (ref "IC1") (pin "14") (pinfunction "PA4_14") (pintype "bidirectional"))
    )
    (net (code "66") (name "unconnected-(IC1-PA5-Pad15)") (class "Default")
      (node (ref "IC1") (pin "15") (pinfunction "PA5_15") (pintype "bidirectional"))
    )
    (net (code "67") (name "unconnected-(IC1-PA7-Pad17)") (class "Default")
      (node (ref "IC1") (pin "17") (pinfunction "PA7_17") (pintype "bidirectional"))
    )
    (net (code "68") (name "unconnected-(IC1-PA8-Pad29)") (class "Default")
      (node (ref "IC1") (pin "29") (pinfunction "PA8_29") (pintype "bidirectional"))
    )
    (net (code "69") (name "unconnected-(IC1-PA11-Pad32)") (class "Default")
      (node (ref "IC1") (pin "32") (pinfunction "PA11_32") (pintype "bidirectional"))
    )
    (net (code "70") (name "unconnected-(IC1-PA15-Pad38)") (class "Default")
      (node (ref "IC1") (pin "38") (pinfunction "PA15_38") (pintype "bidirectional"))
    )
    (net (code "71") (name "unconnected-(IC1-PB0-Pad18)") (class "Default")
      (node (ref "IC1") (pin "18") (pinfunction "PB0_18") (pintype "bidirectional"))
    )
    (net (code "72") (name "unconnected-(IC1-PB1-Pad19)") (class "Default")
      (node (ref "IC1") (pin "19") (pinfunction "PB1_19") (pintype "bidirectional"))
    )
    (net (code "73") (name "unconnected-(IC1-PB2-Pad20)") (class "Default")
      (node (ref "IC1") (pin "20") (pinfunction "PB2_20") (pintype "bidirectional"))
    )
    (net (code "74") (name "unconnected-(IC1-PB9-Pad46)") (class "Default")
      (node (ref "IC1") (pin "46") (pinfunction "PB9_46") (pintype "bidirectional"))
    )
    (net (code "75") (name "unconnected-(IC1-PB10-Pad21)") (class "Default")
      (node (ref "IC1") (pin "21") (pinfunction "PB10_21") (pintype "bidirectional"))
    )
    (net (code "76") (name "unconnected-(IC1-PB11-Pad22)") (class "Default")
      (node (ref "IC1") (pin "22") (pinfunction "PB11_22") (pintype "bidirectional"))
    )
    (net (code "77") (name "unconnected-(IC1-PC13-Pad2)") (class "Default")
      (node (ref "IC1") (pin "2") (pinfunction "PC13_2") (pintype "bidirectional"))
    )
    (net (code "78") (name "unconnected-(IC1-PC14-OSC32_IN-Pad3)") (class "Default")
      (node (ref "IC1") (pin "3") (pinfunction "PC14-OSC32_IN_3") (pintype "bidirectional"))
    )
    (net (code "79") (name "unconnected-(IC1-PC15-OSC32_OUT-Pad4)") (class "Default")
      (node (ref "IC1") (pin "4") (pinfunction "PC15-OSC32_OUT_4") (pintype "bidirectional"))
    )
    (net (code "80") (name "unconnected-(IC1-PF1-OSC_OUT-Pad6)") (class "Default")
      (node (ref "IC1") (pin "6") (pinfunction "PF1-OSC_OUT_6") (pintype "bidirectional"))
    )
    (net (code "81") (name "unconnected-(IC1-PF6-Pad35)") (class "Default")
      (node (ref "IC1") (pin "35") (pinfunction "PF6_35") (pintype "bidirectional"))
    )
    (net (code "82") (name "unconnected-(IC1-PF7-Pad36)") (class "Default")
      (node (ref "IC1") (pin "36") (pinfunction "PF7_36") (pintype "bidirectional"))
    )
    (net (code "83") (name "unconnected-(K1A-S-Pad12A)") (class "Default")
      (node (ref "K1") (pin "12A") (pinfunction "S_12A") (pintype "passive"))
    )
    (net (code "84") (name "unconnected-(K1B-S-Pad12B)") (class "Default")
      (node (ref "K1") (pin "12B") (pinfunction "S_12B") (pintype "passive"))
    )
    (net (code "85") (name "unconnected-(K6A-S-Pad12A)") (class "Default")
      (node (ref "K6") (pin "12A") (pinfunction "S_12A") (pintype "passive"))
    )
    (net (code "86") (name "unconnected-(K6B-S-Pad12B)") (class "Default")
      (node (ref "K6") (pin "12B") (pinfunction "S_12B") (pintype "passive"))
    )
    (net (code "87") (name "unconnected-(X2-Pad1)") (class "Default")
      (node (ref "X2") (pin "1") (pinfunction "1_1") (pintype "passive"))
    )
    (net (code "88") (name "unconnected-(X2L-1-Pad2)") (class "Default")
      (node (ref "X2") (pin "2") (pinfunction "1_2") (pintype "passive"))
    )
    (net (code "89") (name "unconnected-(X2V-1-Pad3)") (class "Default")
      (node (ref "X2") (pin "3") (pinfunction "1_3") (pintype "passive"))
    )
  )
)
